# Teensy_Interface.net
KiCad netlist of a schematic drawn in Altium Designer
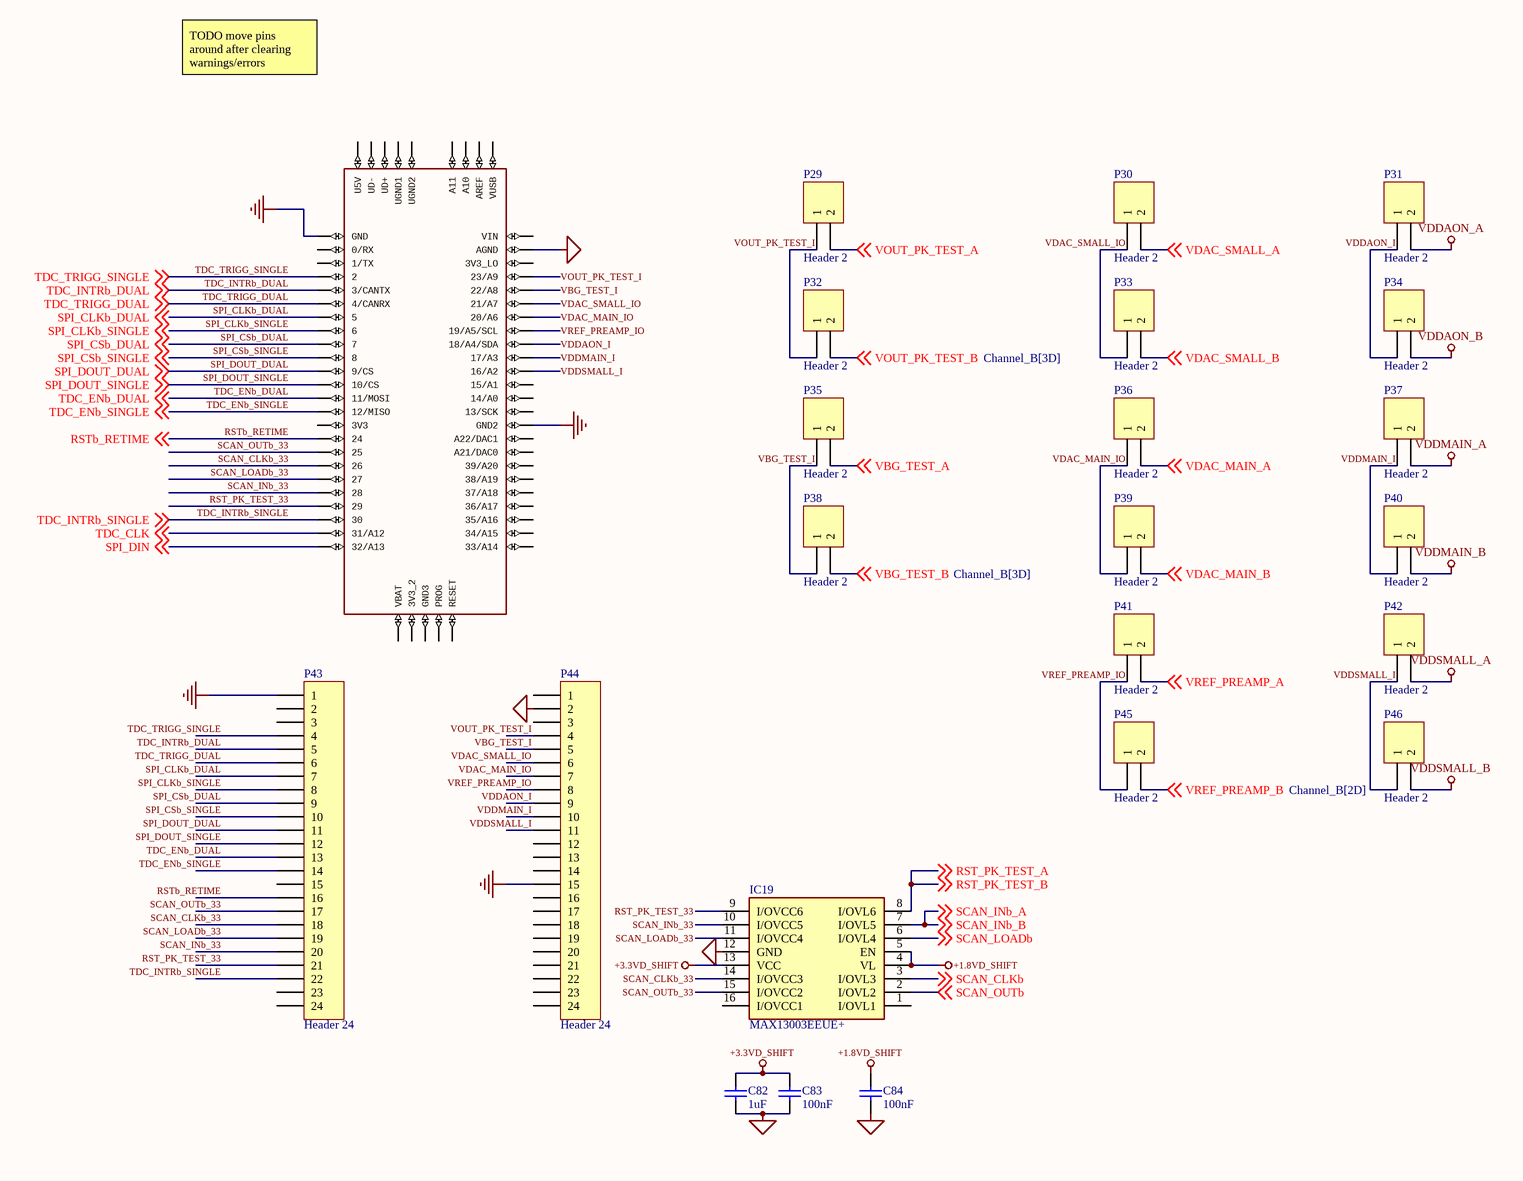
[diagram p0: Teensy_Interface.SchDoc]

(export (version "E")
  (design (tool "Eeschema 10.0.6"))
  (components
    (comp (ref "C82")
      (value "1uF")
      (footprint "CAPC1608X90X35ML10T15")
      (description "0603")
      (fields (field (name "MANUFACTURER") "Murata"))
      (libsource (lib "Altium Content Vault") (part "CAP-NP-2"))
    )
    (comp (ref "C83")
      (value "100nF")
      (footprint "CAPC1608X90X35ML10T15")
      (description "0603")
      (fields (field (name "MANUFACTURER") "Murata"))
      (libsource (lib "Altium Content Vault") (part "CAP-NP-2"))
    )
    (comp (ref "C84")
      (value "100nF")
      (footprint "CAPC1608X90X35ML10T15")
      (description "0603")
      (fields (field (name "MANUFACTURER") "Murata"))
      (libsource (lib "Altium Content Vault") (part "CAP-NP-2"))
    )
    (comp (ref "IC19")
      (value "MAX13003EEUE+")
      (footprint "SamacSys:SOP65P640X110-16N")
      (description "Integrated Circuit")
      (libsource (lib "*") (part "MAX13003EEUE+"))
    )
    (comp (ref "P29")
      (value "Header 2")
      (footprint "HDR1X2")
      (description "Header, 2-Pin")
      (fields (field (name "PUBLISHER") "Altium Limited"))
      (libsource (lib "Miscellaneous Connectors") (part "Header 2"))
    )
    (comp (ref "P30")
      (value "Header 2")
      (footprint "HDR1X2")
      (description "Header, 2-Pin")
      (fields (field (name "PUBLISHER") "Altium Limited"))
      (libsource (lib "Miscellaneous Connectors") (part "Header 2"))
    )
    (comp (ref "P31")
      (value "Header 2")
      (footprint "HDR1X2")
      (description "Header, 2-Pin")
      (fields (field (name "PUBLISHER") "Altium Limited"))
      (libsource (lib "Miscellaneous Connectors") (part "Header 2"))
    )
    (comp (ref "P32")
      (value "Header 2")
      (footprint "HDR1X2")
      (description "Header, 2-Pin")
      (fields (field (name "PUBLISHER") "Altium Limited"))
      (libsource (lib "Miscellaneous Connectors") (part "Header 2"))
    )
    (comp (ref "P33")
      (value "Header 2")
      (footprint "HDR1X2")
      (description "Header, 2-Pin")
      (fields (field (name "PUBLISHER") "Altium Limited"))
      (libsource (lib "Miscellaneous Connectors") (part "Header 2"))
    )
    (comp (ref "P34")
      (value "Header 2")
      (footprint "HDR1X2")
      (description "Header, 2-Pin")
      (fields (field (name "PUBLISHER") "Altium Limited"))
      (libsource (lib "Miscellaneous Connectors") (part "Header 2"))
    )
    (comp (ref "P35")
      (value "Header 2")
      (footprint "HDR1X2")
      (description "Header, 2-Pin")
      (fields (field (name "PUBLISHER") "Altium Limited"))
      (libsource (lib "Miscellaneous Connectors") (part "Header 2"))
    )
    (comp (ref "P36")
      (value "Header 2")
      (footprint "HDR1X2")
      (description "Header, 2-Pin")
      (fields (field (name "PUBLISHER") "Altium Limited"))
      (libsource (lib "Miscellaneous Connectors") (part "Header 2"))
    )
    (comp (ref "P37")
      (value "Header 2")
      (footprint "HDR1X2")
      (description "Header, 2-Pin")
      (fields (field (name "PUBLISHER") "Altium Limited"))
      (libsource (lib "Miscellaneous Connectors") (part "Header 2"))
    )
    (comp (ref "P38")
      (value "Header 2")
      (footprint "HDR1X2")
      (description "Header, 2-Pin")
      (fields (field (name "PUBLISHER") "Altium Limited"))
      (libsource (lib "Miscellaneous Connectors") (part "Header 2"))
    )
    (comp (ref "P39")
      (value "Header 2")
      (footprint "HDR1X2")
      (description "Header, 2-Pin")
      (fields (field (name "PUBLISHER") "Altium Limited"))
      (libsource (lib "Miscellaneous Connectors") (part "Header 2"))
    )
    (comp (ref "P40")
      (value "Header 2")
      (footprint "HDR1X2")
      (description "Header, 2-Pin")
      (fields (field (name "PUBLISHER") "Altium Limited"))
      (libsource (lib "Miscellaneous Connectors") (part "Header 2"))
    )
    (comp (ref "P41")
      (value "Header 2")
      (footprint "HDR1X2")
      (description "Header, 2-Pin")
      (fields (field (name "PUBLISHER") "Altium Limited"))
      (libsource (lib "Miscellaneous Connectors") (part "Header 2"))
    )
    (comp (ref "P42")
      (value "Header 2")
      (footprint "HDR1X2")
      (description "Header, 2-Pin")
      (fields (field (name "PUBLISHER") "Altium Limited"))
      (libsource (lib "Miscellaneous Connectors") (part "Header 2"))
    )
    (comp (ref "P43")
      (value "Header 24")
      (footprint "HDR1X24")
      (description "Header, 24-Pin")
      (fields (field (name "PUBLISHER") "Altium Limited"))
      (libsource (lib "Miscellaneous Connectors") (part "Header 24"))
    )
    (comp (ref "P44")
      (value "Header 24")
      (footprint "HDR1X24")
      (description "Header, 24-Pin")
      (fields (field (name "PUBLISHER") "Altium Limited"))
      (libsource (lib "Miscellaneous Connectors") (part "Header 24"))
    )
    (comp (ref "P45")
      (value "Header 2")
      (footprint "HDR1X2")
      (description "Header, 2-Pin")
      (fields (field (name "PUBLISHER") "Altium Limited"))
      (libsource (lib "Miscellaneous Connectors") (part "Header 2"))
    )
    (comp (ref "P46")
      (value "Header 2")
      (footprint "HDR1X2")
      (description "Header, 2-Pin")
      (fields (field (name "PUBLISHER") "Altium Limited"))
      (libsource (lib "Miscellaneous Connectors") (part "Header 2"))
    )
    (comp (ref "TEENSY1")
      (value "TEENSY_3.5/3.6")
      (footprint "TEENSY_3.5/3.6")
      (libsource (lib "Teensy356") (part "TEENSY_3.5/3.6"))
    )
  )
  (nets
    (net (code "1") (name "+1.8VD_SHIFT") (class "Default")
      (node (ref "C84") (pin "1") (pinfunction "1_1") (pintype "passive"))
      (node (ref "IC19") (pin "4") (pinfunction "VL_4") (pintype "passive"))
      (node (ref "IC19") (pin "5") (pinfunction "EN_5") (pintype "passive"))
    )
    (net (code "2") (name "+3.3VD_SHIFT") (class "Default")
      (node (ref "C82") (pin "2") (pinfunction "2_2") (pintype "passive"))
      (node (ref "C83") (pin "2") (pinfunction "2_2") (pintype "passive"))
      (node (ref "IC19") (pin "13") (pinfunction "VCC_13") (pintype "passive"))
    )
    (net (code "3") (name "/RST_PK_TEST_33") (class "Default")
      (node (ref "IC19") (pin "9") (pinfunction "I/OVCC6_9") (pintype "passive"))
      (node (ref "P43") (pin "21") (pinfunction "21_21") (pintype "passive"))
      (node (ref "TEENSY1") (pin "29") (pinfunction "29_29") (pintype "bidirectional"))
    )
    (net (code "4") (name "/SCAN_CLKb_33") (class "Default")
      (node (ref "IC19") (pin "14") (pinfunction "I/OVCC3_14") (pintype "passive"))
      (node (ref "P43") (pin "18") (pinfunction "18_18") (pintype "passive"))
      (node (ref "TEENSY1") (pin "26") (pinfunction "26_26") (pintype "bidirectional"))
    )
    (net (code "5") (name "/SCAN_INb_33") (class "Default")
      (node (ref "IC19") (pin "10") (pinfunction "I/OVCC5_10") (pintype "passive"))
      (node (ref "P43") (pin "20") (pinfunction "20_20") (pintype "passive"))
      (node (ref "TEENSY1") (pin "28") (pinfunction "28_28") (pintype "bidirectional"))
    )
    (net (code "6") (name "/SCAN_LOADb_33") (class "Default")
      (node (ref "IC19") (pin "11") (pinfunction "I/OVCC4_11") (pintype "passive"))
      (node (ref "P43") (pin "19") (pinfunction "19_19") (pintype "passive"))
      (node (ref "TEENSY1") (pin "27") (pinfunction "27_27") (pintype "bidirectional"))
    )
    (net (code "7") (name "/SCAN_OUTb_33") (class "Default")
      (node (ref "IC19") (pin "15") (pinfunction "I/OVCC2_15") (pintype "passive"))
      (node (ref "P43") (pin "17") (pinfunction "17_17") (pintype "passive"))
      (node (ref "TEENSY1") (pin "25") (pinfunction "25_25") (pintype "bidirectional"))
    )
    (net (code "8") (name "/VBG_TEST_I") (class "Default")
      (node (ref "P35") (pin "1") (pinfunction "1_1") (pintype "passive"))
      (node (ref "P38") (pin "1") (pinfunction "1_1") (pintype "passive"))
      (node (ref "P44") (pin "5") (pinfunction "5_5") (pintype "passive"))
      (node (ref "TEENSY1") (pin "22/A8") (pinfunction "22/A8_22/A8") (pintype "bidirectional"))
    )
    (net (code "9") (name "/VDAC_MAIN_IO") (class "Default")
      (node (ref "P36") (pin "1") (pinfunction "1_1") (pintype "passive"))
      (node (ref "P39") (pin "1") (pinfunction "1_1") (pintype "passive"))
      (node (ref "P44") (pin "7") (pinfunction "7_7") (pintype "passive"))
      (node (ref "TEENSY1") (pin "20/A6") (pinfunction "20/A6_20/A6") (pintype "bidirectional"))
    )
    (net (code "10") (name "/VDAC_SMALL_IO") (class "Default")
      (node (ref "P30") (pin "1") (pinfunction "1_1") (pintype "passive"))
      (node (ref "P33") (pin "1") (pinfunction "1_1") (pintype "passive"))
      (node (ref "P44") (pin "6") (pinfunction "6_6") (pintype "passive"))
      (node (ref "TEENSY1") (pin "21/A7") (pinfunction "21/A7_21/A7") (pintype "bidirectional"))
    )
    (net (code "11") (name "/VDDAON_I") (class "Default")
      (node (ref "P31") (pin "1") (pinfunction "1_1") (pintype "passive"))
      (node (ref "P34") (pin "1") (pinfunction "1_1") (pintype "passive"))
      (node (ref "P44") (pin "9") (pinfunction "9_9") (pintype "passive"))
      (node (ref "TEENSY1") (pin "18/A4/SDA") (pinfunction "18/A4/SDA_18/A4/SDA") (pintype "bidirectional"))
    )
    (net (code "12") (name "/VDDMAIN_I") (class "Default")
      (node (ref "P37") (pin "1") (pinfunction "1_1") (pintype "passive"))
      (node (ref "P40") (pin "1") (pinfunction "1_1") (pintype "passive"))
      (node (ref "P44") (pin "10") (pinfunction "10_10") (pintype "passive"))
      (node (ref "TEENSY1") (pin "17/A3") (pinfunction "17/A3_17/A3") (pintype "bidirectional"))
    )
    (net (code "13") (name "/VDDSMALL_I") (class "Default")
      (node (ref "P42") (pin "1") (pinfunction "1_1") (pintype "passive"))
      (node (ref "P44") (pin "11") (pinfunction "11_11") (pintype "passive"))
      (node (ref "P46") (pin "1") (pinfunction "1_1") (pintype "passive"))
      (node (ref "TEENSY1") (pin "16/A2") (pinfunction "16/A2_16/A2") (pintype "bidirectional"))
    )
    (net (code "14") (name "/VOUT_PK_TEST_I") (class "Default")
      (node (ref "P29") (pin "1") (pinfunction "1_1") (pintype "passive"))
      (node (ref "P32") (pin "1") (pinfunction "1_1") (pintype "passive"))
      (node (ref "P44") (pin "4") (pinfunction "4_4") (pintype "passive"))
      (node (ref "TEENSY1") (pin "23/A9") (pinfunction "23/A9_23/A9") (pintype "bidirectional"))
    )
    (net (code "15") (name "/VREF_PREAMP_IO") (class "Default")
      (node (ref "P41") (pin "1") (pinfunction "1_1") (pintype "passive"))
      (node (ref "P44") (pin "8") (pinfunction "8_8") (pintype "passive"))
      (node (ref "P45") (pin "1") (pinfunction "1_1") (pintype "passive"))
      (node (ref "TEENSY1") (pin "19/A5/SCL") (pinfunction "19/A5/SCL_19/A5/SCL") (pintype "bidirectional"))
    )
    (net (code "16") (name "GND") (class "Default")
      (node (ref "C82") (pin "1") (pinfunction "1_1") (pintype "passive"))
      (node (ref "C83") (pin "1") (pinfunction "1_1") (pintype "passive"))
      (node (ref "C84") (pin "2") (pinfunction "2_2") (pintype "passive"))
      (node (ref "IC19") (pin "12") (pinfunction "GND_12") (pintype "passive"))
      (node (ref "P43") (pin "1") (pinfunction "1_1") (pintype "passive"))
      (node (ref "P44") (pin "15") (pinfunction "15_15") (pintype "passive"))
      (node (ref "P44") (pin "2") (pinfunction "2_2") (pintype "passive"))
      (node (ref "TEENSY1") (pin "AGND") (pinfunction "AGND_AGND") (pintype "bidirectional"))
      (node (ref "TEENSY1") (pin "GND") (pinfunction "GND_GND") (pintype "bidirectional"))
      (node (ref "TEENSY1") (pin "GND2") (pinfunction "GND2_GND2") (pintype "bidirectional"))
    )
    (net (code "17") (name "RST_PK_TEST_A") (class "Default")
      (node (ref "IC19") (pin "8") (pinfunction "I/OVL6_8") (pintype "passive"))
    )
    (net (code "18") (name "RSTb_RETIME") (class "Default")
      (node (ref "P43") (pin "16") (pinfunction "16_16") (pintype "passive"))
      (node (ref "TEENSY1") (pin "24") (pinfunction "24_24") (pintype "bidirectional"))
    )
    (net (code "19") (name "SCAN_CLKb") (class "Default")
      (node (ref "IC19") (pin "3") (pinfunction "I/OVL3_3") (pintype "passive"))
    )
    (net (code "20") (name "SCAN_INb_A") (class "Default")
      (node (ref "IC19") (pin "7") (pinfunction "I/OVL5_7") (pintype "passive"))
    )
    (net (code "21") (name "SCAN_LOADb") (class "Default")
      (node (ref "IC19") (pin "6") (pinfunction "I/OVL4_6") (pintype "passive"))
    )
    (net (code "22") (name "SCAN_OUTb") (class "Default")
      (node (ref "IC19") (pin "2") (pinfunction "I/OVL2_2") (pintype "passive"))
    )
    (net (code "23") (name "SPI_CLKb_DUAL") (class "Default")
      (node (ref "P43") (pin "7") (pinfunction "7_7") (pintype "passive"))
      (node (ref "TEENSY1") (pin "5") (pinfunction "5_5") (pintype "bidirectional"))
    )
    (net (code "24") (name "SPI_CLKb_SINGLE") (class "Default")
      (node (ref "P43") (pin "8") (pinfunction "8_8") (pintype "passive"))
      (node (ref "TEENSY1") (pin "6") (pinfunction "6_6") (pintype "bidirectional"))
    )
    (net (code "25") (name "SPI_CSb_DUAL") (class "Default")
      (node (ref "P43") (pin "9") (pinfunction "9_9") (pintype "passive"))
      (node (ref "TEENSY1") (pin "7") (pinfunction "7_7") (pintype "bidirectional"))
    )
    (net (code "26") (name "SPI_CSb_SINGLE") (class "Default")
      (node (ref "P43") (pin "10") (pinfunction "10_10") (pintype "passive"))
      (node (ref "TEENSY1") (pin "8") (pinfunction "8_8") (pintype "bidirectional"))
    )
    (net (code "27") (name "SPI_DIN") (class "Default")
      (node (ref "TEENSY1") (pin "32/A13") (pinfunction "32/A13_32/A13") (pintype "bidirectional"))
    )
    (net (code "28") (name "SPI_DOUT_DUAL") (class "Default")
      (node (ref "P43") (pin "11") (pinfunction "11_11") (pintype "passive"))
      (node (ref "TEENSY1") (pin "9/CS") (pinfunction "9/CS_9/CS") (pintype "bidirectional"))
    )
    (net (code "29") (name "SPI_DOUT_SINGLE") (class "Default")
      (node (ref "P43") (pin "12") (pinfunction "12_12") (pintype "passive"))
      (node (ref "TEENSY1") (pin "10/CS") (pinfunction "10/CS_10/CS") (pintype "bidirectional"))
    )
    (net (code "30") (name "TDC_CLK") (class "Default")
      (node (ref "TEENSY1") (pin "31/A12") (pinfunction "31/A12_31/A12") (pintype "bidirectional"))
    )
    (net (code "31") (name "TDC_ENb_DUAL") (class "Default")
      (node (ref "P43") (pin "13") (pinfunction "13_13") (pintype "passive"))
      (node (ref "TEENSY1") (pin "11/MOSI") (pinfunction "11/MOSI_11/MOSI") (pintype "bidirectional"))
    )
    (net (code "32") (name "TDC_ENb_SINGLE") (class "Default")
      (node (ref "P43") (pin "14") (pinfunction "14_14") (pintype "passive"))
      (node (ref "TEENSY1") (pin "12/MISO") (pinfunction "12/MISO_12/MISO") (pintype "bidirectional"))
    )
    (net (code "33") (name "TDC_INTRb_DUAL") (class "Default")
      (node (ref "P43") (pin "5") (pinfunction "5_5") (pintype "passive"))
      (node (ref "TEENSY1") (pin "3/CANTX") (pinfunction "3/CANTX_3/CANTX") (pintype "bidirectional"))
    )
    (net (code "34") (name "TDC_INTRb_SINGLE") (class "Default")
      (node (ref "P43") (pin "22") (pinfunction "22_22") (pintype "passive"))
      (node (ref "TEENSY1") (pin "30") (pinfunction "30_30") (pintype "bidirectional"))
    )
    (net (code "35") (name "TDC_TRIGG_DUAL") (class "Default")
      (node (ref "P43") (pin "6") (pinfunction "6_6") (pintype "passive"))
      (node (ref "TEENSY1") (pin "4/CANRX") (pinfunction "4/CANRX_4/CANRX") (pintype "bidirectional"))
    )
    (net (code "36") (name "TDC_TRIGG_SINGLE") (class "Default")
      (node (ref "P43") (pin "4") (pinfunction "4_4") (pintype "passive"))
      (node (ref "TEENSY1") (pin "2") (pinfunction "2_2") (pintype "bidirectional"))
    )
    (net (code "37") (name "VBG_TEST_A") (class "Default")
      (node (ref "P35") (pin "2") (pinfunction "2_2") (pintype "passive"))
    )
    (net (code "38") (name "VBG_TEST_B") (class "Default")
      (node (ref "P38") (pin "2") (pinfunction "2_2") (pintype "passive"))
    )
    (net (code "39") (name "VDAC_MAIN_A") (class "Default")
      (node (ref "P36") (pin "2") (pinfunction "2_2") (pintype "passive"))
    )
    (net (code "40") (name "VDAC_MAIN_B") (class "Default")
      (node (ref "P39") (pin "2") (pinfunction "2_2") (pintype "passive"))
    )
    (net (code "41") (name "VDAC_SMALL_A") (class "Default")
      (node (ref "P30") (pin "2") (pinfunction "2_2") (pintype "passive"))
    )
    (net (code "42") (name "VDAC_SMALL_B") (class "Default")
      (node (ref "P33") (pin "2") (pinfunction "2_2") (pintype "passive"))
    )
    (net (code "43") (name "VDDAON_A") (class "Default")
      (node (ref "P31") (pin "2") (pinfunction "2_2") (pintype "passive"))
    )
    (net (code "44") (name "VDDAON_B") (class "Default")
      (node (ref "P34") (pin "2") (pinfunction "2_2") (pintype "passive"))
    )
    (net (code "45") (name "VDDMAIN_A") (class "Default")
      (node (ref "P37") (pin "2") (pinfunction "2_2") (pintype "passive"))
    )
    (net (code "46") (name "VDDMAIN_B") (class "Default")
      (node (ref "P40") (pin "2") (pinfunction "2_2") (pintype "passive"))
    )
    (net (code "47") (name "VDDSMALL_A") (class "Default")
      (node (ref "P42") (pin "2") (pinfunction "2_2") (pintype "passive"))
    )
    (net (code "48") (name "VDDSMALL_B") (class "Default")
      (node (ref "P46") (pin "2") (pinfunction "2_2") (pintype "passive"))
    )
    (net (code "49") (name "VOUT_PK_TEST_A") (class "Default")
      (node (ref "P29") (pin "2") (pinfunction "2_2") (pintype "passive"))
    )
    (net (code "50") (name "VOUT_PK_TEST_B") (class "Default")
      (node (ref "P32") (pin "2") (pinfunction "2_2") (pintype "passive"))
    )
    (net (code "51") (name "VREF_PREAMP_A") (class "Default")
      (node (ref "P41") (pin "2") (pinfunction "2_2") (pintype "passive"))
    )
    (net (code "52") (name "VREF_PREAMP_B") (class "Default")
      (node (ref "P45") (pin "2") (pinfunction "2_2") (pintype "passive"))
    )
    (net (code "53") (name "unconnected-(IC19-I{slash}OVCC1-Pad16)") (class "Default")
      (node (ref "IC19") (pin "16") (pinfunction "I/OVCC1_16") (pintype "passive"))
    )
    (net (code "54") (name "unconnected-(IC19-I{slash}OVL1-Pad1)") (class "Default")
      (node (ref "IC19") (pin "1") (pinfunction "I/OVL1_1") (pintype "passive"))
    )
    (net (code "55") (name "unconnected-(P43-Pad2)") (class "Default")
      (node (ref "P43") (pin "2") (pinfunction "2_2") (pintype "passive"))
    )
    (net (code "56") (name "unconnected-(P43-Pad3)") (class "Default")
      (node (ref "P43") (pin "3") (pinfunction "3_3") (pintype "passive"))
    )
    (net (code "57") (name "unconnected-(P43-Pad15)") (class "Default")
      (node (ref "P43") (pin "15") (pinfunction "15_15") (pintype "passive"))
    )
    (net (code "58") (name "unconnected-(P43-Pad23)") (class "Default")
      (node (ref "P43") (pin "23") (pinfunction "23_23") (pintype "passive"))
    )
    (net (code "59") (name "unconnected-(P43-Pad24)") (class "Default")
      (node (ref "P43") (pin "24") (pinfunction "24_24") (pintype "passive"))
    )
    (net (code "60") (name "unconnected-(P44-Pad1)") (class "Default")
      (node (ref "P44") (pin "1") (pinfunction "1_1") (pintype "passive"))
    )
    (net (code "61") (name "unconnected-(P44-Pad3)") (class "Default")
      (node (ref "P44") (pin "3") (pinfunction "3_3") (pintype "passive"))
    )
    (net (code "62") (name "unconnected-(P44-Pad12)") (class "Default")
      (node (ref "P44") (pin "12") (pinfunction "12_12") (pintype "passive"))
    )
    (net (code "63") (name "unconnected-(P44-Pad13)") (class "Default")
      (node (ref "P44") (pin "13") (pinfunction "13_13") (pintype "passive"))
    )
    (net (code "64") (name "unconnected-(P44-Pad14)") (class "Default")
      (node (ref "P44") (pin "14") (pinfunction "14_14") (pintype "passive"))
    )
    (net (code "65") (name "unconnected-(P44-Pad16)") (class "Default")
      (node (ref "P44") (pin "16") (pinfunction "16_16") (pintype "passive"))
    )
    (net (code "66") (name "unconnected-(P44-Pad17)") (class "Default")
      (node (ref "P44") (pin "17") (pinfunction "17_17") (pintype "passive"))
    )
    (net (code "67") (name "unconnected-(P44-Pad18)") (class "Default")
      (node (ref "P44") (pin "18") (pinfunction "18_18") (pintype "passive"))
    )
    (net (code "68") (name "unconnected-(P44-Pad19)") (class "Default")
      (node (ref "P44") (pin "19") (pinfunction "19_19") (pintype "passive"))
    )
    (net (code "69") (name "unconnected-(P44-Pad20)") (class "Default")
      (node (ref "P44") (pin "20") (pinfunction "20_20") (pintype "passive"))
    )
    (net (code "70") (name "unconnected-(P44-Pad21)") (class "Default")
      (node (ref "P44") (pin "21") (pinfunction "21_21") (pintype "passive"))
    )
    (net (code "71") (name "unconnected-(P44-Pad22)") (class "Default")
      (node (ref "P44") (pin "22") (pinfunction "22_22") (pintype "passive"))
    )
    (net (code "72") (name "unconnected-(P44-Pad23)") (class "Default")
      (node (ref "P44") (pin "23") (pinfunction "23_23") (pintype "passive"))
    )
    (net (code "73") (name "unconnected-(P44-Pad24)") (class "Default")
      (node (ref "P44") (pin "24") (pinfunction "24_24") (pintype "passive"))
    )
    (net (code "74") (name "unconnected-(TEENSY1-A21{slash}DAC0-Pad21{slash}DAC0)") (class "Default")
      (node (ref "TEENSY1") (pin "21/DAC0") (pinfunction "A21/DAC0_21/DAC0") (pintype "bidirectional"))
    )
    (net (code "75") (name "unconnected-(TEENSY1-Pad0{slash}RX)") (class "Default")
      (node (ref "TEENSY1") (pin "0/RX") (pinfunction "0/RX_0/RX") (pintype "bidirectional"))
    )
    (net (code "76") (name "unconnected-(TEENSY1-Pad1{slash}TX)") (class "Default")
      (node (ref "TEENSY1") (pin "1/TX") (pinfunction "1/TX_1/TX") (pintype "bidirectional"))
    )
    (net (code "77") (name "unconnected-(TEENSY1-Pad3V3)") (class "Default")
      (node (ref "TEENSY1") (pin "3V3") (pinfunction "3V3_3V3") (pintype "bidirectional"))
    )
    (net (code "78") (name "unconnected-(TEENSY1-Pad3V3_2)") (class "Default")
      (node (ref "TEENSY1") (pin "3V3_2") (pinfunction "3V3_2_3V3_2") (pintype "bidirectional"))
    )
    (net (code "79") (name "unconnected-(TEENSY1-Pad3V3_LO)") (class "Default")
      (node (ref "TEENSY1") (pin "3V3_LO") (pinfunction "3V3_LO_3V3_LO") (pintype "bidirectional"))
    )
    (net (code "80") (name "unconnected-(TEENSY1-Pad13{slash}SCK)") (class "Default")
      (node (ref "TEENSY1") (pin "13/SCK") (pinfunction "13/SCK_13/SCK") (pintype "bidirectional"))
    )
    (net (code "81") (name "unconnected-(TEENSY1-Pad14{slash}A0)") (class "Default")
      (node (ref "TEENSY1") (pin "14/A0") (pinfunction "14/A0_14/A0") (pintype "bidirectional"))
    )
    (net (code "82") (name "unconnected-(TEENSY1-Pad15{slash}A1)") (class "Default")
      (node (ref "TEENSY1") (pin "15/A1") (pinfunction "15/A1_15/A1") (pintype "bidirectional"))
    )
    (net (code "83") (name "unconnected-(TEENSY1-Pad33{slash}A14)") (class "Default")
      (node (ref "TEENSY1") (pin "33/A14") (pinfunction "33/A14_33/A14") (pintype "bidirectional"))
    )
    (net (code "84") (name "unconnected-(TEENSY1-Pad34{slash}A15)") (class "Default")
      (node (ref "TEENSY1") (pin "34/A15") (pinfunction "34/A15_34/A15") (pintype "bidirectional"))
    )
    (net (code "85") (name "unconnected-(TEENSY1-Pad35{slash}A16)") (class "Default")
      (node (ref "TEENSY1") (pin "35/A16") (pinfunction "35/A16_35/A16") (pintype "bidirectional"))
    )
    (net (code "86") (name "unconnected-(TEENSY1-Pad36{slash}A17)") (class "Default")
      (node (ref "TEENSY1") (pin "36/A17") (pinfunction "36/A17_36/A17") (pintype "bidirectional"))
    )
    (net (code "87") (name "unconnected-(TEENSY1-Pad37{slash}A18)") (class "Default")
      (node (ref "TEENSY1") (pin "37/A18") (pinfunction "37/A18_37/A18") (pintype "bidirectional"))
    )
    (net (code "88") (name "unconnected-(TEENSY1-Pad38{slash}A19)") (class "Default")
      (node (ref "TEENSY1") (pin "38/A19") (pinfunction "38/A19_38/A19") (pintype "bidirectional"))
    )
    (net (code "89") (name "unconnected-(TEENSY1-Pad39{slash}A20)") (class "Default")
      (node (ref "TEENSY1") (pin "39/A20") (pinfunction "39/A20_39/A20") (pintype "bidirectional"))
    )
    (net (code "90") (name "unconnected-(TEENSY1-PadA10)") (class "Default")
      (node (ref "TEENSY1") (pin "A10") (pinfunction "A10_A10") (pintype "bidirectional"))
    )
    (net (code "91") (name "unconnected-(TEENSY1-PadA11)") (class "Default")
      (node (ref "TEENSY1") (pin "A11") (pinfunction "A11_A11") (pintype "bidirectional"))
    )
    (net (code "92") (name "unconnected-(TEENSY1-PadA22{slash}DAC1)") (class "Default")
      (node (ref "TEENSY1") (pin "A22/DAC1") (pinfunction "A22/DAC1_A22/DAC1") (pintype "bidirectional"))
    )
    (net (code "93") (name "unconnected-(TEENSY1-PadAREF)") (class "Default")
      (node (ref "TEENSY1") (pin "AREF") (pinfunction "AREF_AREF") (pintype "bidirectional"))
    )
    (net (code "94") (name "unconnected-(TEENSY1-PadGND3)") (class "Default")
      (node (ref "TEENSY1") (pin "GND3") (pinfunction "GND3_GND3") (pintype "bidirectional"))
    )
    (net (code "95") (name "unconnected-(TEENSY1-PadPROG)") (class "Default")
      (node (ref "TEENSY1") (pin "PROG") (pinfunction "PROG_PROG") (pintype "bidirectional"))
    )
    (net (code "96") (name "unconnected-(TEENSY1-PadRESET)") (class "Default")
      (node (ref "TEENSY1") (pin "RESET") (pinfunction "RESET_RESET") (pintype "bidirectional"))
    )
    (net (code "97") (name "unconnected-(TEENSY1-PadU5V)") (class "Default")
      (node (ref "TEENSY1") (pin "U5V") (pinfunction "U5V_U5V") (pintype "bidirectional"))
    )
    (net (code "98") (name "unconnected-(TEENSY1-PadUD+)") (class "Default")
      (node (ref "TEENSY1") (pin "UD+") (pinfunction "UD+_UD+") (pintype "bidirectional"))
    )
    (net (code "99") (name "unconnected-(TEENSY1-PadUD-)") (class "Default")
      (node (ref "TEENSY1") (pin "UD-") (pinfunction "UD-_UD-") (pintype "bidirectional"))
    )
    (net (code "100") (name "unconnected-(TEENSY1-PadUGND1)") (class "Default")
      (node (ref "TEENSY1") (pin "UGND1") (pinfunction "UGND1_UGND1") (pintype "bidirectional"))
    )
    (net (code "101") (name "unconnected-(TEENSY1-PadUGND2)") (class "Default")
      (node (ref "TEENSY1") (pin "UGND2") (pinfunction "UGND2_UGND2") (pintype "bidirectional"))
    )
    (net (code "102") (name "unconnected-(TEENSY1-PadVBAT)") (class "Default")
      (node (ref "TEENSY1") (pin "VBAT") (pinfunction "VBAT_VBAT") (pintype "bidirectional"))
    )
    (net (code "103") (name "unconnected-(TEENSY1-PadVIN)") (class "Default")
      (node (ref "TEENSY1") (pin "VIN") (pinfunction "VIN_VIN") (pintype "bidirectional"))
    )
    (net (code "104") (name "unconnected-(TEENSY1-PadVUSB)") (class "Default")
      (node (ref "TEENSY1") (pin "VUSB") (pinfunction "VUSB_VUSB") (pintype "bidirectional"))
    )
  )
)
